# ESC_Main.net
KiCad netlist of a schematic drawn in Altium Designer
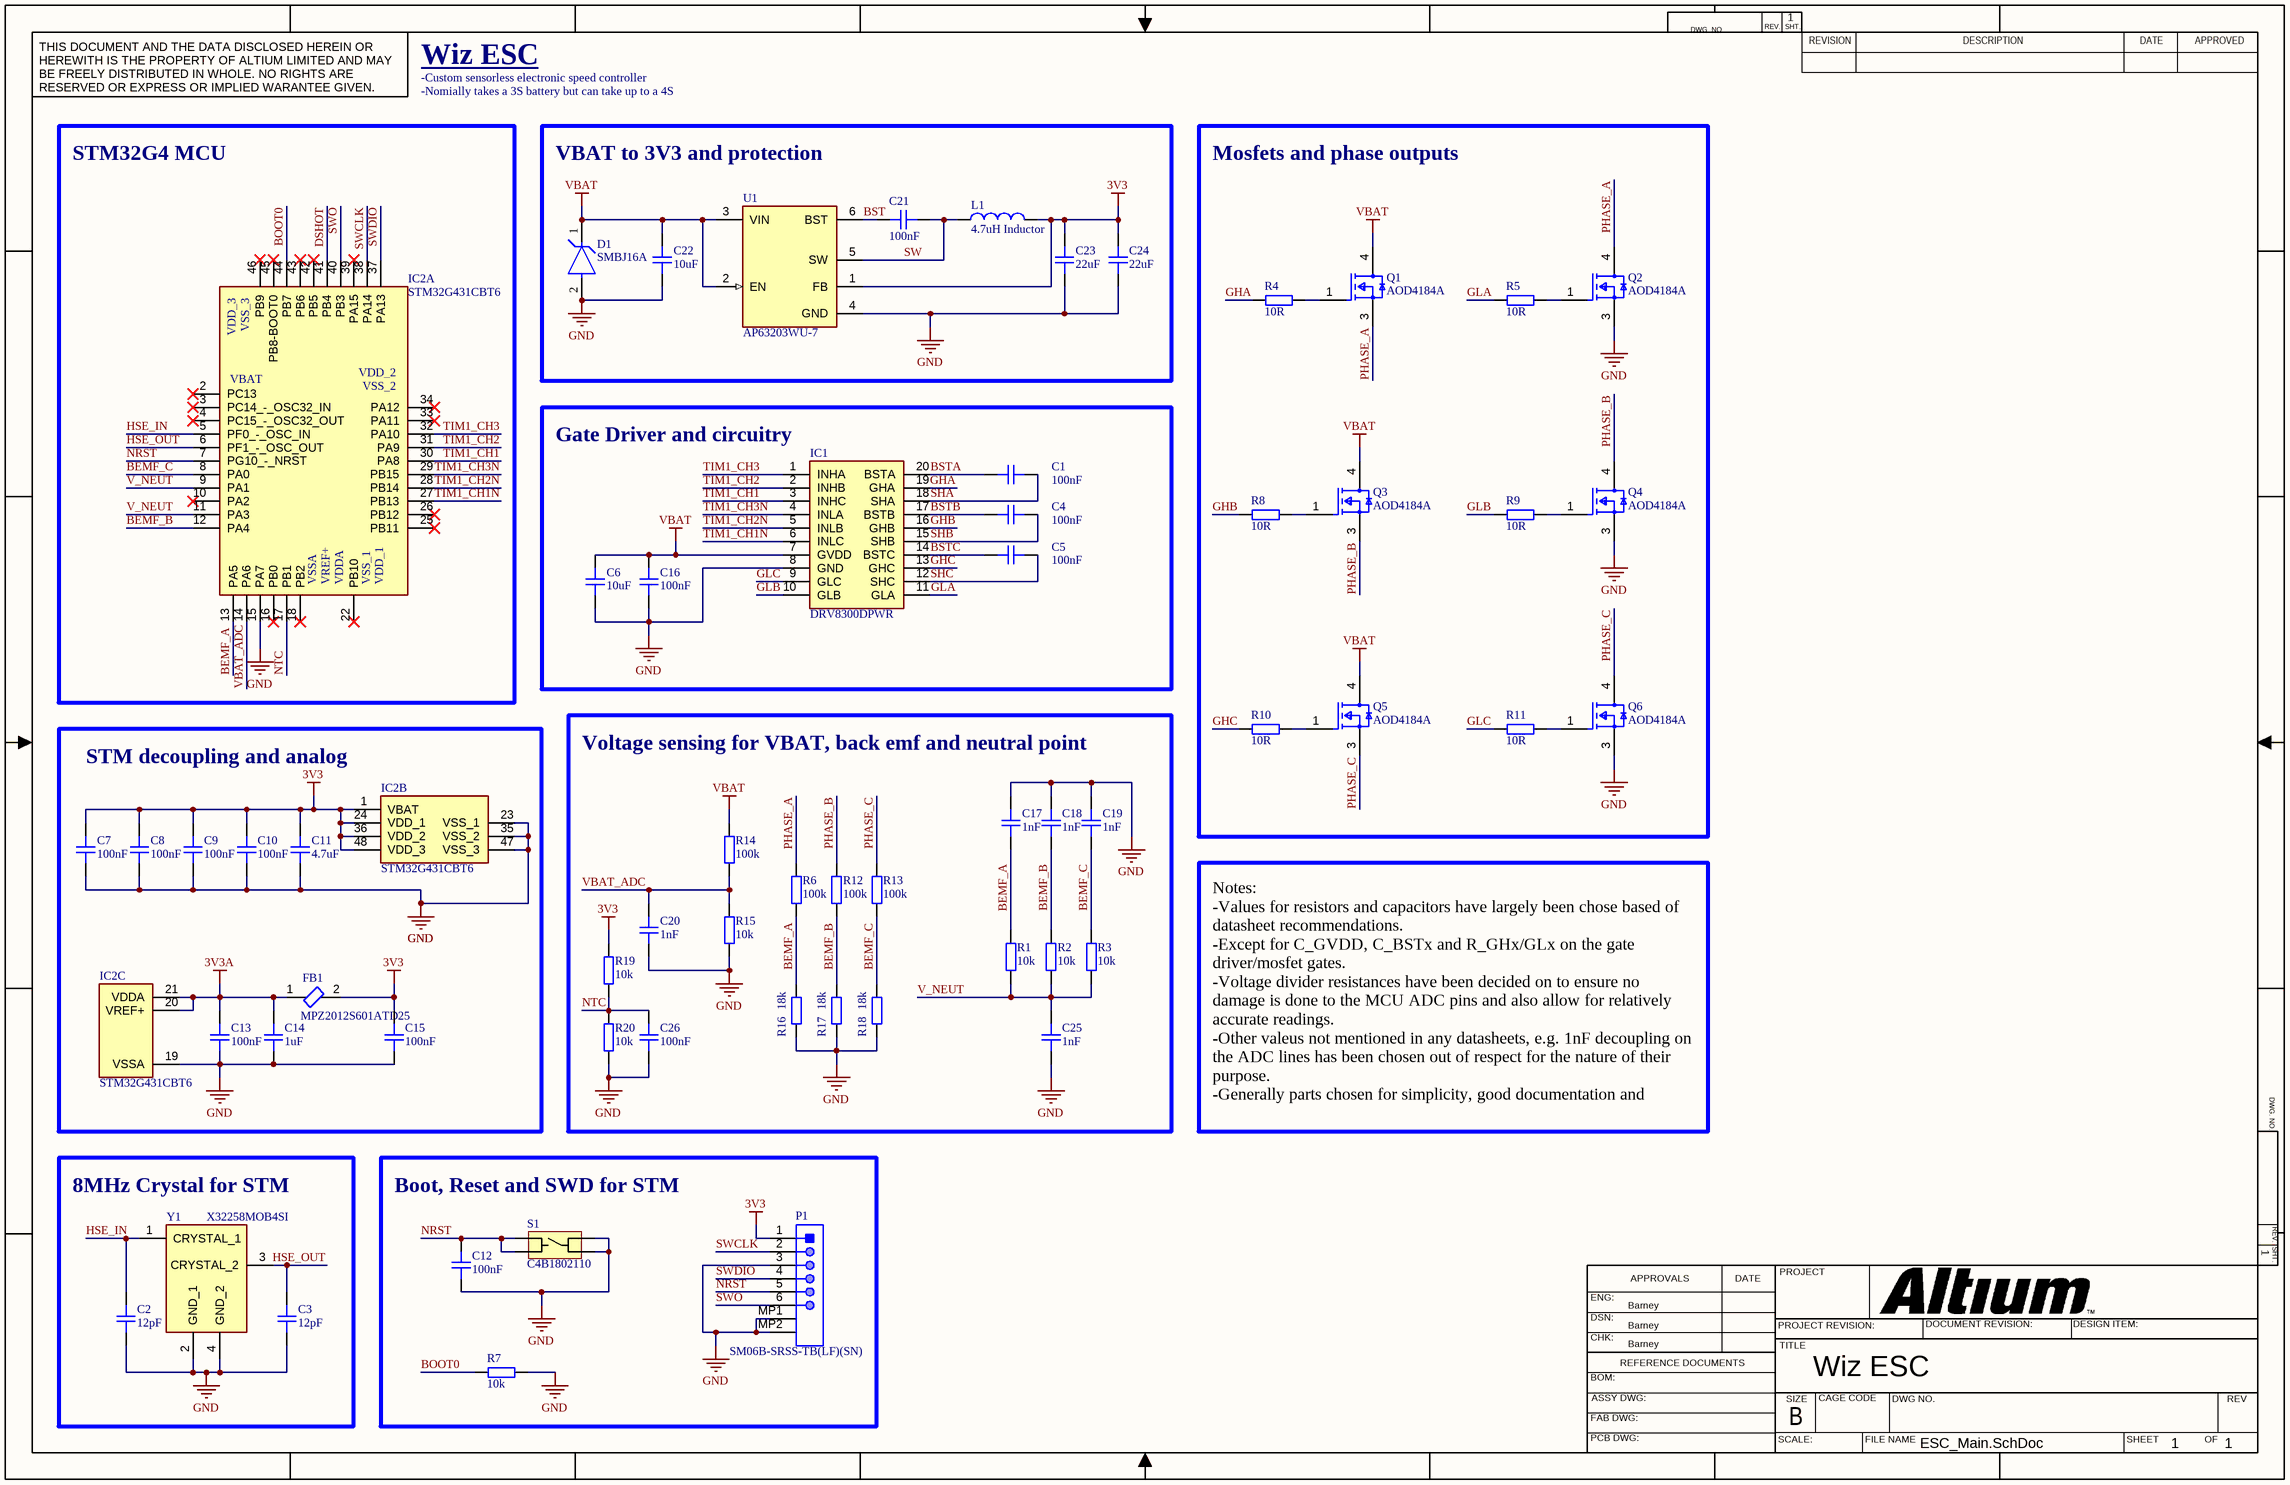
[diagram p0: ESC_Main.SchDoc]

(export (version "E")
  (design (tool "Eeschema 10.0.6"))
  (components
    (comp (ref "C1")
      (value "100nF")
      (footprint "CAP_0402")
      (description "Capacitor SMD 0402")
      (fields
        (field (name "MANUFACTURER") "Samsung Electro-Mechanics")
        (field (name "MANUFACTURER PART NUMBER") "CL05B104KB5NNNC")
      )
      (libsource (lib "BRye_SCHLib") (part "CAP_0402"))
    )
    (comp (ref "C2")
      (value "12pF")
      (footprint "CAP_0402")
      (description "Capacitor SMD 0402")
      (fields
        (field (name "MANUFACTURER") "Samsung Electro-Mechanics")
        (field (name "MANUFACTURER PART NUMBER") "CL05C120JB5NNNC")
      )
      (libsource (lib "BRye_SCHLib") (part "CAP_0402"))
    )
    (comp (ref "C3")
      (value "12pF")
      (footprint "CAP_0402")
      (description "Capacitor SMD 0402")
      (fields
        (field (name "MANUFACTURER") "Samsung Electro-Mechanics")
        (field (name "MANUFACTURER PART NUMBER") "CL05C120JB5NNNC")
      )
      (libsource (lib "BRye_SCHLib") (part "CAP_0402"))
    )
    (comp (ref "C4")
      (value "100nF")
      (footprint "CAP_0402")
      (description "Capacitor SMD 0402")
      (fields
        (field (name "MANUFACTURER") "Samsung Electro-Mechanics")
        (field (name "MANUFACTURER PART NUMBER") "CL05B104KB5NNNC")
      )
      (libsource (lib "BRye_SCHLib") (part "CAP_0402"))
    )
    (comp (ref "C5")
      (value "100nF")
      (footprint "CAP_0402")
      (description "Capacitor SMD 0402")
      (fields
        (field (name "MANUFACTURER") "Samsung Electro-Mechanics")
        (field (name "MANUFACTURER PART NUMBER") "CL05B104KB5NNNC")
      )
      (libsource (lib "BRye_SCHLib") (part "CAP_0402"))
    )
    (comp (ref "C6")
      (value "10uF")
      (footprint "CAP_1206")
      (description "Capacitor SMD 1206")
      (fields
        (field (name "MANUFACTURER") "Samsung Electro-Mechanics")
        (field (name "MANUFACTURER PART NUMBER") "CL31Y106KBKVPNE")
      )
      (libsource (lib "BRye_SCHLib") (part "CAP_1206"))
    )
    (comp (ref "C7")
      (value "100nF")
      (footprint "CAP_0402")
      (description "Capacitor SMD 0402")
      (fields
        (field (name "MANUFACTURER") "Samsung Electro-Mechanics")
        (field (name "MANUFACTURER PART NUMBER") "CL05A104KA5NNNC")
      )
      (libsource (lib "BRye_SCHLib") (part "CAP_0402"))
    )
    (comp (ref "C8")
      (value "100nF")
      (footprint "CAP_0402")
      (description "Capacitor SMD 0402")
      (fields
        (field (name "MANUFACTURER") "Samsung Electro-Mechanics")
        (field (name "MANUFACTURER PART NUMBER") "CL05A104KA5NNNC")
      )
      (libsource (lib "BRye_SCHLib") (part "CAP_0402"))
    )
    (comp (ref "C9")
      (value "100nF")
      (footprint "CAP_0402")
      (description "Capacitor SMD 0402")
      (fields
        (field (name "MANUFACTURER") "Samsung Electro-Mechanics")
        (field (name "MANUFACTURER PART NUMBER") "CL05A104KA5NNNC")
      )
      (libsource (lib "BRye_SCHLib") (part "CAP_0402"))
    )
    (comp (ref "C10")
      (value "100nF")
      (footprint "CAP_0402")
      (description "Capacitor SMD 0402")
      (fields
        (field (name "MANUFACTURER") "Samsung Electro-Mechanics")
        (field (name "MANUFACTURER PART NUMBER") "CL05A104KA5NNNC")
      )
      (libsource (lib "BRye_SCHLib") (part "CAP_0402"))
    )
    (comp (ref "C11")
      (value "4.7uF")
      (footprint "CAP_0402")
      (description "Capacitor SMD 0402")
      (fields
        (field (name "MANUFACTURER") "Samsung Electro-Mechanics")
        (field (name "MANUFACTURER PART NUMBER") "CL05A475KP5NRNC")
      )
      (libsource (lib "BRye_SCHLib") (part "CAP_0402"))
    )
    (comp (ref "C12")
      (value "100nF")
      (footprint "CAP_0402")
      (description "Capacitor SMD 0402")
      (fields
        (field (name "MANUFACTURER") "Samsung Electro-Mechanics")
        (field (name "MANUFACTURER PART NUMBER") "CL05A104KA5NNNC")
      )
      (libsource (lib "BRye_SCHLib") (part "CAP_0402"))
    )
    (comp (ref "C13")
      (value "100nF")
      (footprint "CAP_0402")
      (description "Capacitor SMD 0402")
      (fields
        (field (name "MANUFACTURER") "Samsung Electro-Mechanics")
        (field (name "MANUFACTURER PART NUMBER") "CL05A104KA5NNNC")
      )
      (libsource (lib "BRye_SCHLib") (part "CAP_0402"))
    )
    (comp (ref "C14")
      (value "1uF")
      (footprint "CAP_0402")
      (description "Capacitor SMD 0402")
      (fields
        (field (name "MANUFACTURER") "Samsung Electro-Mechanics")
        (field (name "MANUFACTURER PART NUMBER") "CL05A105KA5NQNC")
      )
      (libsource (lib "") (part "CAP_0402_1"))
    )
    (comp (ref "C15")
      (value "100nF")
      (footprint "CAP_0402")
      (description "Capacitor SMD 0402")
      (fields
        (field (name "MANUFACTURER") "Samsung Electro-Mechanics")
        (field (name "MANUFACTURER PART NUMBER") "CL05A104KA5NNNC")
      )
      (libsource (lib "BRye_SCHLib") (part "CAP_0402"))
    )
    (comp (ref "C16")
      (value "100nF")
      (footprint "CAP_0402")
      (description "Capacitor SMD 0402")
      (fields
        (field (name "MANUFACTURER") "Samsung Electro-Mechanics")
        (field (name "MANUFACTURER PART NUMBER") "CL05B104KB5NNNC")
      )
      (libsource (lib "BRye_SCHLib") (part "CAP_0402"))
    )
    (comp (ref "C17")
      (value "1nF")
      (footprint "CAP_0402")
      (description "Capacitor SMD 0402")
      (fields
        (field (name "MANUFACTURER") "Samsung Electro-Mechanics")
        (field (name "MANUFACTURER PART NUMBER") "CL05B102KB5NNNC")
      )
      (libsource (lib "BRye_SCHLib") (part "CAP_0402"))
    )
    (comp (ref "C18")
      (value "1nF")
      (footprint "CAP_0402")
      (description "Capacitor SMD 0402")
      (fields
        (field (name "MANUFACTURER") "Samsung Electro-Mechanics")
        (field (name "MANUFACTURER PART NUMBER") "CL05B102KB5NNNC")
      )
      (libsource (lib "BRye_SCHLib") (part "CAP_0402"))
    )
    (comp (ref "C19")
      (value "1nF")
      (footprint "CAP_0402")
      (description "Capacitor SMD 0402")
      (fields
        (field (name "MANUFACTURER") "Samsung Electro-Mechanics")
        (field (name "MANUFACTURER PART NUMBER") "CL05B102KB5NNNC")
      )
      (libsource (lib "BRye_SCHLib") (part "CAP_0402"))
    )
    (comp (ref "C20")
      (value "1nF")
      (footprint "CAP_0402")
      (description "Capacitor SMD 0402")
      (fields
        (field (name "MANUFACTURER") "Samsung Electro-Mechanics")
        (field (name "MANUFACTURER PART NUMBER") "CL05B102KB5NNNC")
      )
      (libsource (lib "BRye_SCHLib") (part "CAP_0402"))
    )
    (comp (ref "C21")
      (value "100nF")
      (footprint "CAP_0402")
      (description "Capacitor SMD 0402")
      (fields
        (field (name "MANUFACTURER") "Samsung Electro-Mechanics")
        (field (name "MANUFACTURER PART NUMBER") "CL05B104KB5NNNC")
      )
      (libsource (lib "BRye_SCHLib") (part "CAP_0402"))
    )
    (comp (ref "C22")
      (value "10uF")
      (footprint "CAP_1206")
      (description "Capacitor SMD 1206")
      (fields
        (field (name "MANUFACTURER") "Samsung Electro-Mechanics")
        (field (name "MANUFACTURER PART NUMBER") "CL31Y106KBKVPNE")
      )
      (libsource (lib "BRye_SCHLib") (part "CAP_1206"))
    )
    (comp (ref "C23")
      (value "22uF")
      (footprint "CAP_0402")
      (description "Capacitor SMD 0402")
      (fields
        (field (name "MANUFACTURER") "Samsung Electro-Mechanics")
        (field (name "MANUFACTURER PART NUMBER") "CL10A226MO7JZNC")
      )
      (libsource (lib "BRye_SCHLib") (part "CAP_0402"))
    )
    (comp (ref "C24")
      (value "22uF")
      (footprint "CAP_0402")
      (description "Capacitor SMD 0402")
      (fields
        (field (name "MANUFACTURER") "Samsung Electro-Mechanics")
        (field (name "MANUFACTURER PART NUMBER") "CL10A226MO7JZNC")
      )
      (libsource (lib "BRye_SCHLib") (part "CAP_0402"))
    )
    (comp (ref "C25")
      (value "1nF")
      (footprint "CAP_0402")
      (description "Capacitor SMD 0402")
      (fields
        (field (name "MANUFACTURER") "Samsung Electro-Mechanics")
        (field (name "MANUFACTURER PART NUMBER") "CL05B102KB5NNNC")
      )
      (libsource (lib "BRye_SCHLib") (part "CAP_0402"))
    )
    (comp (ref "C26")
      (value "100nF")
      (footprint "CAP_0402")
      (description "Capacitor SMD 0402")
      (fields
        (field (name "MANUFACTURER") "Samsung Electro-Mechanics")
        (field (name "MANUFACTURER PART NUMBER") "CL05B104KB5NNNC")
      )
      (libsource (lib "BRye_SCHLib") (part "CAP_0402"))
    )
    (comp (ref "D1")
      (value "SMBJ16A")
      (footprint "FP-DO-214AA-MFG")
      (description "TVS DIODE 16VWM 26VC SMBJ")
      (fields (field (name "MANUFACTURER") "Jingdao Microelectronics"))
      (libsource (lib "Altium Content Vault") (part "f813f71cba58e380607f5dd3caf9714"))
    )
    (comp (ref "FB1")
      (value "MPZ2012S601ATD25")
      (footprint "SamacSys:BEADC2112X105N")
      (description "Ferrite Beads 600 @ 100MHz 0805")
      (fields (field (name "MANUFACTURER") "TDK"))
      (libsource (lib "BRye_SCHLib") (part "GZ2012D601TF"))
    )
    (comp (ref "IC1")
      (value "DRV8300DPWR")
      (footprint "SamacSys:SOP65P640X120-20N")
      (description "Integrated Circuit")
      (fields
        (field (name "MANUFACTURER") "Texas Instruments")
        (field (name "MOUSER PART NUMBER") "595-DRV8300DPWR")
      )
      (libsource (lib "*") (part "DRV8300DPWR"))
    )
    (comp (ref "IC2")
      (value "STM32G431CBT6")
      (footprint "SamacSys:QFP50P900X900X160-48N")
      (description "Integrated Circuit")
      (fields
        (field (name "MANUFACTURER") "STMicroelectronics")
        (field (name "MANUFACTURER PART NUMBER") "STM32G431CBT6TR")
        (field (name "MOUSER PART NUMBER") "511-STM32G431CBT6")
      )
      (libsource (lib "BRye_SCHLib") (part "STM32G474CBT6"))
    )
    (comp (ref "L1")
      (value "4.7uH Inductor")
      (footprint "SMD 8x8 Inductor")
      (description "5.9A 4.7uH 5.9A 24mΩ Magnetic Shielded Inductor ±20% SMD,8x8mm Fixed Inductors RoHS")
      (fields
        (field (name "MANUFACTURER") "Shun Xiang Nuo")
        (field (name "MANUFACTURER PART NUMBER") "SMNR8040-4R7MT")
      )
      (libsource (lib "BRye_SCHLib") (part "SMNR8040-4R7MT"))
    )
    (comp (ref "P1")
      (value "SM06B-SRSS-TB(LF)(SN)")
      (footprint "JST-SM06B-SRSS-TB_V")
      (description "Male Header, Pitch 1 mm, 1 x 6 Position, Height 2.95 mm, -25 to 85 degC, RoHS, Tape and Reel")
      (fields (field (name "MANUFACTURER") "JST"))
      (libsource (lib "Altium Content Vault") (part "CN-1P-2M-R6"))
    )
    (comp (ref "Q1")
      (value "AOD4184A")
      (footprint "FP-TO252-MFG")
      (description "MOSFET N-CH 40V 50A TO252")
      (libsource (lib "Altium Content Vault") (part "eaf820099600a16e7148a0c70285cb7"))
    )
    (comp (ref "Q2")
      (value "AOD4184A")
      (footprint "FP-TO252-MFG")
      (description "MOSFET N-CH 40V 50A TO252")
      (libsource (lib "Altium Content Vault") (part "eaf820099600a16e7148a0c70285cb7"))
    )
    (comp (ref "Q3")
      (value "AOD4184A")
      (footprint "FP-TO252-MFG")
      (description "MOSFET N-CH 40V 50A TO252")
      (libsource (lib "Altium Content Vault") (part "eaf820099600a16e7148a0c70285cb7"))
    )
    (comp (ref "Q4")
      (value "AOD4184A")
      (footprint "FP-TO252-MFG")
      (description "MOSFET N-CH 40V 50A TO252")
      (libsource (lib "Altium Content Vault") (part "eaf820099600a16e7148a0c70285cb7"))
    )
    (comp (ref "Q5")
      (value "AOD4184A")
      (footprint "FP-TO252-MFG")
      (description "MOSFET N-CH 40V 50A TO252")
      (fields (field (name "MANUFACTURER") "AOS"))
      (libsource (lib "Altium Content Vault") (part "eaf820099600a16e7148a0c70285cb7"))
    )
    (comp (ref "Q6")
      (value "AOD4184A")
      (footprint "FP-TO252-MFG")
      (description "MOSFET N-CH 40V 50A TO252")
      (libsource (lib "Altium Content Vault") (part "eaf820099600a16e7148a0c70285cb7"))
    )
    (comp (ref "R1")
      (value "10k")
      (footprint "RES_0402")
      (description "Resistor SMD 0402")
      (fields
        (field (name "MANUFACTURER") "FOJAN")
        (field (name "MANUFACTURER PART NUMBER") "FRC0402F1002TS")
      )
      (libsource (lib "BRye_SCHLib") (part "RES_0402"))
    )
    (comp (ref "R2")
      (value "10k")
      (footprint "RES_0402")
      (description "Resistor SMD 0402")
      (fields
        (field (name "MANUFACTURER") "FOJAN")
        (field (name "MANUFACTURER PART NUMBER") "FRC0402F1002TS")
      )
      (libsource (lib "BRye_SCHLib") (part "RES_0402"))
    )
    (comp (ref "R3")
      (value "10k")
      (footprint "RES_0402")
      (description "Resistor SMD 0402")
      (fields
        (field (name "MANUFACTURER") "FOJAN")
        (field (name "MANUFACTURER PART NUMBER") "FRC0402F1002TS")
      )
      (libsource (lib "BRye_SCHLib") (part "RES_0402"))
    )
    (comp (ref "R4")
      (value "10R")
      (footprint "RES_0402")
      (description "Resistor SMD 0402")
      (fields
        (field (name "MANUFACTURER") "FOJAN")
        (field (name "MANUFACTURER PART NUMBER") "FRC0402F10R0TS")
      )
      (libsource (lib "BRye_SCHLib") (part "RES_0402"))
    )
    (comp (ref "R5")
      (value "10R")
      (footprint "RES_0402")
      (description "Resistor SMD 0402")
      (fields
        (field (name "MANUFACTURER") "FOJAN")
        (field (name "MANUFACTURER PART NUMBER") "FRC0402F10R0TS")
      )
      (libsource (lib "BRye_SCHLib") (part "RES_0402"))
    )
    (comp (ref "R6")
      (value "100k")
      (footprint "RES_0603")
      (description "Resistor SMD 0603")
      (fields
        (field (name "MANUFACTURER") "FOJAN")
        (field (name "MANUFACTURER PART NUMBER") "FRC0603J104 TS")
      )
      (libsource (lib "BRye_SCHLib") (part "RES_0603"))
    )
    (comp (ref "R7")
      (value "10k")
      (footprint "RES_0402")
      (description "Resistor SMD 0402")
      (fields
        (field (name "MANUFACTURER") "FOJAN")
        (field (name "MANUFACTURER PART NUMBER") "FRC0402F1002TS")
      )
      (libsource (lib "BRye_SCHLib") (part "RES_0402"))
    )
    (comp (ref "R8")
      (value "10R")
      (footprint "RES_0402")
      (description "Resistor SMD 0402")
      (fields
        (field (name "MANUFACTURER") "FOJAN")
        (field (name "MANUFACTURER PART NUMBER") "FRC0402F10R0TS")
      )
      (libsource (lib "BRye_SCHLib") (part "RES_0402"))
    )
    (comp (ref "R9")
      (value "10R")
      (footprint "RES_0402")
      (description "Resistor SMD 0402")
      (fields
        (field (name "MANUFACTURER") "FOJAN")
        (field (name "MANUFACTURER PART NUMBER") "FRC0402F10R0TS")
      )
      (libsource (lib "BRye_SCHLib") (part "RES_0402"))
    )
    (comp (ref "R10")
      (value "10R")
      (footprint "RES_0402")
      (description "Resistor SMD 0402")
      (fields
        (field (name "MANUFACTURER") "FOJAN")
        (field (name "MANUFACTURER PART NUMBER") "FRC0402F10R0TS")
      )
      (libsource (lib "BRye_SCHLib") (part "RES_0402"))
    )
    (comp (ref "R11")
      (value "10R")
      (footprint "RES_0402")
      (description "Resistor SMD 0402")
      (fields
        (field (name "MANUFACTURER") "FOJAN")
        (field (name "MANUFACTURER PART NUMBER") "FRC0402F10R0TS")
      )
      (libsource (lib "BRye_SCHLib") (part "RES_0402"))
    )
    (comp (ref "R12")
      (value "100k")
      (footprint "RES_0603")
      (description "Resistor SMD 0603")
      (fields
        (field (name "MANUFACTURER") "FOJAN")
        (field (name "MANUFACTURER PART NUMBER") "FRC0603J104 TS")
      )
      (libsource (lib "BRye_SCHLib") (part "RES_0603"))
    )
    (comp (ref "R13")
      (value "100k")
      (footprint "RES_0603")
      (description "Resistor SMD 0603")
      (fields
        (field (name "MANUFACTURER") "FOJAN")
        (field (name "MANUFACTURER PART NUMBER") "FRC0603J104 TS")
      )
      (libsource (lib "BRye_SCHLib") (part "RES_0603"))
    )
    (comp (ref "R14")
      (value "100k")
      (footprint "RES_0603")
      (description "Resistor SMD 0603")
      (fields
        (field (name "MANUFACTURER") "FOJAN")
        (field (name "MANUFACTURER PART NUMBER") "FRC0603J104 TS")
      )
      (libsource (lib "BRye_SCHLib") (part "RES_0603"))
    )
    (comp (ref "R15")
      (value "10k")
      (footprint "RES_0603")
      (description "Resistor SMD 0603")
      (fields
        (field (name "MANUFACTURER") "FOJAN")
        (field (name "MANUFACTURER PART NUMBER") "FRC0603F1002TS")
      )
      (libsource (lib "BRye_SCHLib") (part "RES_0603"))
    )
    (comp (ref "R16")
      (value "18k")
      (footprint "RES_0603")
      (description "Resistor SMD 0603")
      (fields
        (field (name "MANUFACTURER") "FOJAN")
        (field (name "MANUFACTURER PART NUMBER") "FRC0603F1802TS")
      )
      (libsource (lib "BRye_SCHLib") (part "RES_0603"))
    )
    (comp (ref "R17")
      (value "18k")
      (footprint "RES_0603")
      (description "Resistor SMD 0603")
      (fields
        (field (name "MANUFACTURER") "FOJAN")
        (field (name "MANUFACTURER PART NUMBER") "FRC0603F1802TS")
      )
      (libsource (lib "BRye_SCHLib") (part "RES_0603"))
    )
    (comp (ref "R18")
      (value "18k")
      (footprint "RES_0603")
      (description "Resistor SMD 0603")
      (fields
        (field (name "MANUFACTURER") "FOJAN")
        (field (name "MANUFACTURER PART NUMBER") "FRC0603F1802TS")
      )
      (libsource (lib "BRye_SCHLib") (part "RES_0603"))
    )
    (comp (ref "R19")
      (value "10k")
      (footprint "RES_0402")
      (description "Resistor SMD 0402")
      (fields
        (field (name "MANUFACTURER") "FOJAN")
        (field (name "MANUFACTURER PART NUMBER") "FRC0402F1002TS")
      )
      (libsource (lib "BRye_SCHLib") (part "RES_0402"))
    )
    (comp (ref "R20")
      (value "10k")
      (footprint "RES_0402")
      (description "Resistor SMD 0402")
      (fields
        (field (name "MANUFACTURER") "FOJAN")
        (field (name "MANUFACTURER PART NUMBER") "FRC0402F1002TS")
      )
      (libsource (lib "BRye_SCHLib") (part "RES_0402"))
    )
    (comp (ref "S1")
      (value "C4B1802110")
      (footprint "SW-SMD_4P-L3.5-W3.0-P1.50-LS4.7")
      (description "SMD NO Push Button Switch")
      (fields (field (name "MANUFACTURER") "SAMZO"))
      (libsource (lib "BRye_SCHLib") (part "C4B1802110"))
    )
    (comp (ref "U1")
      (value "AP63203WU-7")
      (footprint "FP-TSOT26-MFG")
      (description "IC REG BUCK 3.3V 2A TSOT26")
      (fields
        (field (name "MANUFACTURER") "Diodes Inc.")
        (field (name "OCTOPART") "https://octopart.com/ap63203wu-7-diodes+inc.-98099550")
      )
      (libsource (lib "Altium Content Vault") (part "0e61c2974d7114b43f01ef96ae2e524"))
    )
    (comp (ref "Y1")
      (value "X32258MOB4SI")
      (footprint "SamacSys:X32258MOB4SI")
      (description "Crystal or Oscillator")
      (fields (field (name "MANUFACTURER") "YXC"))
      (libsource (lib "BRye_SCHLib") (part "X32258MOB4SI"))
    )
  )
  (nets
    (net (code "1") (name "/BEMF_A") (class "Default")
      (node (ref "C17") (pin "2") (pinfunction "2_2") (pintype "passive"))
      (node (ref "IC2") (pin "13") (pinfunction "PA5_13") (pintype "passive"))
      (node (ref "R1") (pin "2") (pinfunction "2_2") (pintype "passive"))
      (node (ref "R16") (pin "2") (pinfunction "2_2") (pintype "passive"))
      (node (ref "R6") (pin "1") (pinfunction "1_1") (pintype "passive"))
    )
    (net (code "2") (name "/BEMF_B") (class "Default")
      (node (ref "C18") (pin "2") (pinfunction "2_2") (pintype "passive"))
      (node (ref "IC2") (pin "12") (pinfunction "PA4_12") (pintype "passive"))
      (node (ref "R12") (pin "1") (pinfunction "1_1") (pintype "passive"))
      (node (ref "R17") (pin "2") (pinfunction "2_2") (pintype "passive"))
      (node (ref "R2") (pin "2") (pinfunction "2_2") (pintype "passive"))
    )
    (net (code "3") (name "/BEMF_C") (class "Default")
      (node (ref "C19") (pin "2") (pinfunction "2_2") (pintype "passive"))
      (node (ref "IC2") (pin "8") (pinfunction "PA0_8") (pintype "passive"))
      (node (ref "R13") (pin "1") (pinfunction "1_1") (pintype "passive"))
      (node (ref "R18") (pin "2") (pinfunction "2_2") (pintype "passive"))
      (node (ref "R3") (pin "2") (pinfunction "2_2") (pintype "passive"))
    )
    (net (code "4") (name "/BOOT0") (class "Default")
      (node (ref "IC2") (pin "44") (pinfunction "PB7_44") (pintype "passive"))
      (node (ref "R7") (pin "1") (pinfunction "1_1") (pintype "passive"))
    )
    (net (code "5") (name "/BST") (class "Default")
      (node (ref "C21") (pin "2") (pinfunction "2_2") (pintype "passive"))
      (node (ref "U1") (pin "6") (pinfunction "BST_6") (pintype "passive"))
    )
    (net (code "6") (name "/BSTA") (class "Default")
      (node (ref "C1") (pin "2") (pinfunction "2_2") (pintype "passive"))
      (node (ref "IC1") (pin "20") (pinfunction "BSTA_20") (pintype "passive"))
    )
    (net (code "7") (name "/BSTB") (class "Default")
      (node (ref "C4") (pin "2") (pinfunction "2_2") (pintype "passive"))
      (node (ref "IC1") (pin "17") (pinfunction "BSTB_17") (pintype "passive"))
    )
    (net (code "8") (name "/BSTC") (class "Default")
      (node (ref "C5") (pin "2") (pinfunction "2_2") (pintype "passive"))
      (node (ref "IC1") (pin "14") (pinfunction "BSTC_14") (pintype "passive"))
    )
    (net (code "9") (name "/DSHOT") (class "Default")
      (node (ref "IC2") (pin "41") (pinfunction "PB4_41") (pintype "passive"))
    )
    (net (code "10") (name "/GHA") (class "Default")
      (node (ref "IC1") (pin "19") (pinfunction "GHA_19") (pintype "passive"))
      (node (ref "R4") (pin "1") (pinfunction "1_1") (pintype "passive"))
    )
    (net (code "11") (name "/GHB") (class "Default")
      (node (ref "IC1") (pin "16") (pinfunction "GHB_16") (pintype "passive"))
      (node (ref "R8") (pin "1") (pinfunction "1_1") (pintype "passive"))
    )
    (net (code "12") (name "/GHC") (class "Default")
      (node (ref "IC1") (pin "13") (pinfunction "GHC_13") (pintype "passive"))
      (node (ref "R10") (pin "1") (pinfunction "1_1") (pintype "passive"))
    )
    (net (code "13") (name "/GLA") (class "Default")
      (node (ref "IC1") (pin "11") (pinfunction "GLA_11") (pintype "passive"))
      (node (ref "R5") (pin "1") (pinfunction "1_1") (pintype "passive"))
    )
    (net (code "14") (name "/GLB") (class "Default")
      (node (ref "IC1") (pin "10") (pinfunction "GLB_10") (pintype "passive"))
      (node (ref "R9") (pin "1") (pinfunction "1_1") (pintype "passive"))
    )
    (net (code "15") (name "/GLC") (class "Default")
      (node (ref "IC1") (pin "9") (pinfunction "GLC_9") (pintype "passive"))
      (node (ref "R11") (pin "1") (pinfunction "1_1") (pintype "passive"))
    )
    (net (code "16") (name "/HSE_IN") (class "Default")
      (node (ref "C2") (pin "1") (pinfunction "1_1") (pintype "passive"))
      (node (ref "IC2") (pin "5") (pinfunction "PF0_-_OSC_IN_5") (pintype "passive"))
      (node (ref "Y1") (pin "1") (pinfunction "CRYSTAL_1_1") (pintype "passive"))
    )
    (net (code "17") (name "/HSE_OUT") (class "Default")
      (node (ref "C3") (pin "1") (pinfunction "1_1") (pintype "passive"))
      (node (ref "IC2") (pin "6") (pinfunction "PF1_-_OSC_OUT_6") (pintype "passive"))
      (node (ref "Y1") (pin "3") (pinfunction "CRYSTAL_2_3") (pintype "passive"))
    )
    (net (code "18") (name "/NRST") (class "Default")
      (node (ref "C12") (pin "1") (pinfunction "1_1") (pintype "passive"))
      (node (ref "IC2") (pin "7") (pinfunction "PG10_-_NRST_7") (pintype "passive"))
      (node (ref "P1") (pin "5") (pinfunction "5_5") (pintype "passive"))
      (node (ref "S1") (pin "1") (pinfunction "1_1") (pintype "passive"))
      (node (ref "S1") (pin "2") (pinfunction "2_2") (pintype "passive"))
    )
    (net (code "19") (name "/NTC") (class "Default")
      (node (ref "C26") (pin "2") (pinfunction "2_2") (pintype "passive"))
      (node (ref "IC2") (pin "17") (pinfunction "PB1_17") (pintype "passive"))
      (node (ref "R19") (pin "1") (pinfunction "1_1") (pintype "passive"))
      (node (ref "R20") (pin "2") (pinfunction "2_2") (pintype "passive"))
    )
    (net (code "20") (name "/PHASE_A") (class "Default")
      (node (ref "Q1") (pin "3") (pinfunction "S_3") (pintype "passive"))
      (node (ref "Q2") (pin "4") (pinfunction "D_4") (pintype "passive"))
      (node (ref "R6") (pin "2") (pinfunction "2_2") (pintype "passive"))
    )
    (net (code "21") (name "/PHASE_B") (class "Default")
      (node (ref "Q3") (pin "3") (pinfunction "S_3") (pintype "passive"))
      (node (ref "Q4") (pin "4") (pinfunction "D_4") (pintype "passive"))
      (node (ref "R12") (pin "2") (pinfunction "2_2") (pintype "passive"))
    )
    (net (code "22") (name "/PHASE_C") (class "Default")
      (node (ref "Q5") (pin "3") (pinfunction "S_3") (pintype "passive"))
      (node (ref "Q6") (pin "4") (pinfunction "D_4") (pintype "passive"))
      (node (ref "R13") (pin "2") (pinfunction "2_2") (pintype "passive"))
    )
    (net (code "23") (name "/SHA") (class "Default")
      (node (ref "C1") (pin "1") (pinfunction "1_1") (pintype "passive"))
      (node (ref "IC1") (pin "18") (pinfunction "SHA_18") (pintype "passive"))
    )
    (net (code "24") (name "/SHB") (class "Default")
      (node (ref "C4") (pin "1") (pinfunction "1_1") (pintype "passive"))
      (node (ref "IC1") (pin "15") (pinfunction "SHB_15") (pintype "passive"))
    )
    (net (code "25") (name "/SHC") (class "Default")
      (node (ref "C5") (pin "1") (pinfunction "1_1") (pintype "passive"))
      (node (ref "IC1") (pin "12") (pinfunction "SHC_12") (pintype "passive"))
    )
    (net (code "26") (name "/SW") (class "Default")
      (node (ref "C21") (pin "1") (pinfunction "1_1") (pintype "passive"))
      (node (ref "L1") (pin "1") (pinfunction "1_1") (pintype "passive"))
      (node (ref "U1") (pin "5") (pinfunction "SW_5") (pintype "passive"))
    )
    (net (code "27") (name "/SWCLK") (class "Default")
      (node (ref "IC2") (pin "38") (pinfunction "PA14_38") (pintype "passive"))
      (node (ref "P1") (pin "2") (pinfunction "2_2") (pintype "passive"))
    )
    (net (code "28") (name "/SWDIO") (class "Default")
      (node (ref "IC2") (pin "37") (pinfunction "PA13_37") (pintype "passive"))
      (node (ref "P1") (pin "4") (pinfunction "4_4") (pintype "passive"))
    )
    (net (code "29") (name "/SWO") (class "Default")
      (node (ref "IC2") (pin "40") (pinfunction "PB3_40") (pintype "passive"))
      (node (ref "P1") (pin "6") (pinfunction "6_6") (pintype "passive"))
    )
    (net (code "30") (name "/TIM1_CH1") (class "Default")
      (node (ref "IC1") (pin "3") (pinfunction "INHC_3") (pintype "passive"))
      (node (ref "IC2") (pin "30") (pinfunction "PA8_30") (pintype "passive"))
    )
    (net (code "31") (name "/TIM1_CH1N") (class "Default")
      (node (ref "IC1") (pin "6") (pinfunction "INLC_6") (pintype "passive"))
      (node (ref "IC2") (pin "27") (pinfunction "PB13_27") (pintype "passive"))
    )
    (net (code "32") (name "/TIM1_CH2") (class "Default")
      (node (ref "IC1") (pin "2") (pinfunction "INHB_2") (pintype "passive"))
      (node (ref "IC2") (pin "31") (pinfunction "PA9_31") (pintype "passive"))
    )
    (net (code "33") (name "/TIM1_CH2N") (class "Default")
      (node (ref "IC1") (pin "5") (pinfunction "INLB_5") (pintype "passive"))
      (node (ref "IC2") (pin "28") (pinfunction "PB14_28") (pintype "passive"))
    )
    (net (code "34") (name "/TIM1_CH3") (class "Default")
      (node (ref "IC1") (pin "1") (pinfunction "INHA_1") (pintype "passive"))
      (node (ref "IC2") (pin "32") (pinfunction "PA10_32") (pintype "passive"))
    )
    (net (code "35") (name "/TIM1_CH3N") (class "Default")
      (node (ref "IC1") (pin "4") (pinfunction "INLA_4") (pintype "passive"))
      (node (ref "IC2") (pin "29") (pinfunction "PB15_29") (pintype "passive"))
    )
    (net (code "36") (name "/VBAT_ADC") (class "Default")
      (node (ref "C20") (pin "1") (pinfunction "1_1") (pintype "passive"))
      (node (ref "IC2") (pin "14") (pinfunction "PA6_14") (pintype "passive"))
      (node (ref "R14") (pin "1") (pinfunction "1_1") (pintype "passive"))
      (node (ref "R15") (pin "2") (pinfunction "2_2") (pintype "passive"))
    )
    (net (code "37") (name "/V_NEUT") (class "Default")
      (node (ref "C25") (pin "1") (pinfunction "1_1") (pintype "passive"))
      (node (ref "IC2") (pin "11") (pinfunction "PA3_11") (pintype "passive"))
      (node (ref "IC2") (pin "9") (pinfunction "PA1_9") (pintype "passive"))
      (node (ref "R1") (pin "1") (pinfunction "1_1") (pintype "passive"))
      (node (ref "R2") (pin "1") (pinfunction "1_1") (pintype "passive"))
      (node (ref "R3") (pin "1") (pinfunction "1_1") (pintype "passive"))
    )
    (net (code "38") (name "3V3") (class "Default")
      (node (ref "C10") (pin "1") (pinfunction "1_1") (pintype "passive"))
      (node (ref "C11") (pin "1") (pinfunction "1_1") (pintype "passive"))
      (node (ref "C15") (pin "1") (pinfunction "1_1") (pintype "passive"))
      (node (ref "C23") (pin "2") (pinfunction "2_2") (pintype "passive"))
      (node (ref "C24") (pin "2") (pinfunction "2_2") (pintype "passive"))
      (node (ref "C7") (pin "1") (pinfunction "1_1") (pintype "passive"))
      (node (ref "C8") (pin "1") (pinfunction "1_1") (pintype "passive"))
      (node (ref "C9") (pin "1") (pinfunction "1_1") (pintype "passive"))
      (node (ref "FB1") (pin "2") (pinfunction "2_2") (pintype "passive"))
      (node (ref "IC2") (pin "1") (pinfunction "VBAT_1") (pintype "passive"))
      (node (ref "IC2") (pin "24") (pinfunction "VDD_1_24") (pintype "passive"))
      (node (ref "IC2") (pin "36") (pinfunction "VDD_2_36") (pintype "passive"))
      (node (ref "IC2") (pin "48") (pinfunction "VDD_3_48") (pintype "passive"))
      (node (ref "L1") (pin "2") (pinfunction "2_2") (pintype "passive"))
      (node (ref "P1") (pin "1") (pinfunction "1_1") (pintype "passive"))
      (node (ref "R19") (pin "2") (pinfunction "2_2") (pintype "passive"))
      (node (ref "U1") (pin "1") (pinfunction "FB_1") (pintype "passive"))
    )
    (net (code "39") (name "3V3A") (class "Default")
      (node (ref "C13") (pin "1") (pinfunction "1_1") (pintype "passive"))
      (node (ref "C14") (pin "2") (pinfunction "2_2") (pintype "passive"))
      (node (ref "FB1") (pin "1") (pinfunction "1_1") (pintype "passive"))
      (node (ref "IC2") (pin "20") (pinfunction "VREF+_20") (pintype "passive"))
      (node (ref "IC2") (pin "21") (pinfunction "VDDA_21") (pintype "passive"))
    )
    (net (code "40") (name "GND") (class "Default")
      (node (ref "C10") (pin "2") (pinfunction "2_2") (pintype "passive"))
      (node (ref "C11") (pin "2") (pinfunction "2_2") (pintype "passive"))
      (node (ref "C12") (pin "2") (pinfunction "2_2") (pintype "passive"))
      (node (ref "C13") (pin "2") (pinfunction "2_2") (pintype "passive"))
      (node (ref "C14") (pin "1") (pinfunction "1_1") (pintype "passive"))
      (node (ref "C15") (pin "2") (pinfunction "2_2") (pintype "passive"))
      (node (ref "C16") (pin "1") (pinfunction "1_1") (pintype "passive"))
      (node (ref "C17") (pin "1") (pinfunction "1_1") (pintype "passive"))
      (node (ref "C18") (pin "1") (pinfunction "1_1") (pintype "passive"))
      (node (ref "C19") (pin "1") (pinfunction "1_1") (pintype "passive"))
      (node (ref "C2") (pin "2") (pinfunction "2_2") (pintype "passive"))
      (node (ref "C20") (pin "2") (pinfunction "2_2") (pintype "passive"))
      (node (ref "C22") (pin "1") (pinfunction "1_1") (pintype "passive"))
      (node (ref "C23") (pin "1") (pinfunction "1_1") (pintype "passive"))
      (node (ref "C24") (pin "1") (pinfunction "1_1") (pintype "passive"))
      (node (ref "C25") (pin "2") (pinfunction "2_2") (pintype "passive"))
      (node (ref "C26") (pin "1") (pinfunction "1_1") (pintype "passive"))
      (node (ref "C3") (pin "2") (pinfunction "2_2") (pintype "passive"))
      (node (ref "C6") (pin "1") (pinfunction "1_1") (pintype "passive"))
      (node (ref "C7") (pin "2") (pinfunction "2_2") (pintype "passive"))
      (node (ref "C8") (pin "2") (pinfunction "2_2") (pintype "passive"))
      (node (ref "C9") (pin "2") (pinfunction "2_2") (pintype "passive"))
      (node (ref "D1") (pin "2") (pinfunction "A_2") (pintype "passive"))
      (node (ref "IC1") (pin "8") (pinfunction "GND_8") (pintype "passive"))
      (node (ref "IC2") (pin "15") (pinfunction "PA7_15") (pintype "passive"))
      (node (ref "IC2") (pin "19") (pinfunction "VSSA_19") (pintype "passive"))
      (node (ref "IC2") (pin "23") (pinfunction "VSS_1_23") (pintype "passive"))
      (node (ref "IC2") (pin "35") (pinfunction "VSS_2_35") (pintype "passive"))
      (node (ref "IC2") (pin "47") (pinfunction "VSS_3_47") (pintype "passive"))
      (node (ref "P1") (pin "3") (pinfunction "3_3") (pintype "passive"))
      (node (ref "P1") (pin "MP1") (pinfunction "MP1_MP1") (pintype "passive"))
      (node (ref "P1") (pin "MP2") (pinfunction "MP2_MP2") (pintype "passive"))
      (node (ref "Q2") (pin "3") (pinfunction "S_3") (pintype "passive"))
      (node (ref "Q4") (pin "3") (pinfunction "S_3") (pintype "passive"))
      (node (ref "Q6") (pin "3") (pinfunction "S_3") (pintype "passive"))
      (node (ref "R15") (pin "1") (pinfunction "1_1") (pintype "passive"))
      (node (ref "R16") (pin "1") (pinfunction "1_1") (pintype "passive"))
      (node (ref "R17") (pin "1") (pinfunction "1_1") (pintype "passive"))
      (node (ref "R18") (pin "1") (pinfunction "1_1") (pintype "passive"))
      (node (ref "R20") (pin "1") (pinfunction "1_1") (pintype "passive"))
      (node (ref "R7") (pin "2") (pinfunction "2_2") (pintype "passive"))
      (node (ref "S1") (pin "3") (pinfunction "3_3") (pintype "passive"))
      (node (ref "S1") (pin "4") (pinfunction "4_4") (pintype "passive"))
      (node (ref "U1") (pin "4") (pinfunction "GND_4") (pintype "power_in"))
      (node (ref "Y1") (pin "2") (pinfunction "GND_1_2") (pintype "passive"))
      (node (ref "Y1") (pin "4") (pinfunction "GND_2_4") (pintype "passive"))
    )
    (net (code "41") (name "Net-(Q1-G)") (class "Default")
      (node (ref "Q1") (pin "1") (pinfunction "G_1") (pintype "passive"))
      (node (ref "R4") (pin "2") (pinfunction "2_2") (pintype "passive"))
    )
    (net (code "42") (name "Net-(Q2-G)") (class "Default")
      (node (ref "Q2") (pin "1") (pinfunction "G_1") (pintype "passive"))
      (node (ref "R5") (pin "2") (pinfunction "2_2") (pintype "passive"))
    )
    (net (code "43") (name "Net-(Q3-G)") (class "Default")
      (node (ref "Q3") (pin "1") (pinfunction "G_1") (pintype "passive"))
      (node (ref "R8") (pin "2") (pinfunction "2_2") (pintype "passive"))
    )
    (net (code "44") (name "Net-(Q4-G)") (class "Default")
      (node (ref "Q4") (pin "1") (pinfunction "G_1") (pintype "passive"))
      (node (ref "R9") (pin "2") (pinfunction "2_2") (pintype "passive"))
    )
    (net (code "45") (name "Net-(Q5-G)") (class "Default")
      (node (ref "Q5") (pin "1") (pinfunction "G_1") (pintype "passive"))
      (node (ref "R10") (pin "2") (pinfunction "2_2") (pintype "passive"))
    )
    (net (code "46") (name "Net-(Q6-G)") (class "Default")
      (node (ref "Q6") (pin "1") (pinfunction "G_1") (pintype "passive"))
      (node (ref "R11") (pin "2") (pinfunction "2_2") (pintype "passive"))
    )
    (net (code "47") (name "VBAT") (class "Default")
      (node (ref "C16") (pin "2") (pinfunction "2_2") (pintype "passive"))
      (node (ref "C22") (pin "2") (pinfunction "2_2") (pintype "passive"))
      (node (ref "C6") (pin "2") (pinfunction "2_2") (pintype "passive"))
      (node (ref "D1") (pin "1") (pinfunction "C_1") (pintype "passive"))
      (node (ref "IC1") (pin "7") (pinfunction "GVDD_7") (pintype "passive"))
      (node (ref "Q1") (pin "4") (pinfunction "D_4") (pintype "passive"))
      (node (ref "Q3") (pin "4") (pinfunction "D_4") (pintype "passive"))
      (node (ref "Q5") (pin "4") (pinfunction "D_4") (pintype "passive"))
      (node (ref "R14") (pin "2") (pinfunction "2_2") (pintype "passive"))
      (node (ref "U1") (pin "2") (pinfunction "EN_2") (pintype "input"))
      (node (ref "U1") (pin "3") (pinfunction "VIN_3") (pintype "power_in"))
    )
    (net (code "48") (name "unconnected-(IC2A-PA2-Pad10)") (class "Default")
      (node (ref "IC2") (pin "10") (pinfunction "PA2_10") (pintype "passive+no_connect"))
    )
    (net (code "49") (name "unconnected-(IC2A-PA11-Pad33)") (class "Default")
      (node (ref "IC2") (pin "33") (pinfunction "PA11_33") (pintype "passive+no_connect"))
    )
    (net (code "50") (name "unconnected-(IC2A-PA12-Pad34)") (class "Default")
      (node (ref "IC2") (pin "34") (pinfunction "PA12_34") (pintype "passive+no_connect"))
    )
    (net (code "51") (name "unconnected-(IC2A-PA15-Pad39)") (class "Default")
      (node (ref "IC2") (pin "39") (pinfunction "PA15_39") (pintype "passive+no_connect"))
    )
    (net (code "52") (name "unconnected-(IC2A-PB0-Pad16)") (class "Default")
      (node (ref "IC2") (pin "16") (pinfunction "PB0_16") (pintype "passive+no_connect"))
    )
    (net (code "53") (name "unconnected-(IC2A-PB2-Pad18)") (class "Default")
      (node (ref "IC2") (pin "18") (pinfunction "PB2_18") (pintype "passive+no_connect"))
    )
    (net (code "54") (name "unconnected-(IC2A-PB5-Pad42)") (class "Default")
      (node (ref "IC2") (pin "42") (pinfunction "PB5_42") (pintype "passive+no_connect"))
    )
    (net (code "55") (name "unconnected-(IC2A-PB6-Pad43)") (class "Default")
      (node (ref "IC2") (pin "43") (pinfunction "PB6_43") (pintype "passive+no_connect"))
    )
    (net (code "56") (name "unconnected-(IC2A-PB8-BOOT0-Pad45)") (class "Default")
      (node (ref "IC2") (pin "45") (pinfunction "PB8-BOOT0_45") (pintype "passive+no_connect"))
    )
    (net (code "57") (name "unconnected-(IC2A-PB9-Pad46)") (class "Default")
      (node (ref "IC2") (pin "46") (pinfunction "PB9_46") (pintype "passive+no_connect"))
    )
    (net (code "58") (name "unconnected-(IC2A-PB10-Pad22)") (class "Default")
      (node (ref "IC2") (pin "22") (pinfunction "PB10_22") (pintype "passive+no_connect"))
    )
    (net (code "59") (name "unconnected-(IC2A-PB11-Pad25)") (class "Default")
      (node (ref "IC2") (pin "25") (pinfunction "PB11_25") (pintype "passive+no_connect"))
    )
    (net (code "60") (name "unconnected-(IC2A-PB12-Pad26)") (class "Default")
      (node (ref "IC2") (pin "26") (pinfunction "PB12_26") (pintype "passive+no_connect"))
    )
    (net (code "61") (name "unconnected-(IC2A-PC13-Pad2)") (class "Default")
      (node (ref "IC2") (pin "2") (pinfunction "PC13_2") (pintype "passive+no_connect"))
    )
    (net (code "62") (name "unconnected-(IC2A-PC14_-_OSC32_IN-Pad3)") (class "Default")
      (node (ref "IC2") (pin "3") (pinfunction "PC14_-_OSC32_IN_3") (pintype "passive+no_connect"))
    )
    (net (code "63") (name "unconnected-(IC2A-PC15_-_OSC32_OUT-Pad4)") (class "Default")
      (node (ref "IC2") (pin "4") (pinfunction "PC15_-_OSC32_OUT_4") (pintype "passive+no_connect"))
    )
  )
)
